# Dot-Matrix.net
KiCad netlist of a schematic drawn in EasyEDA
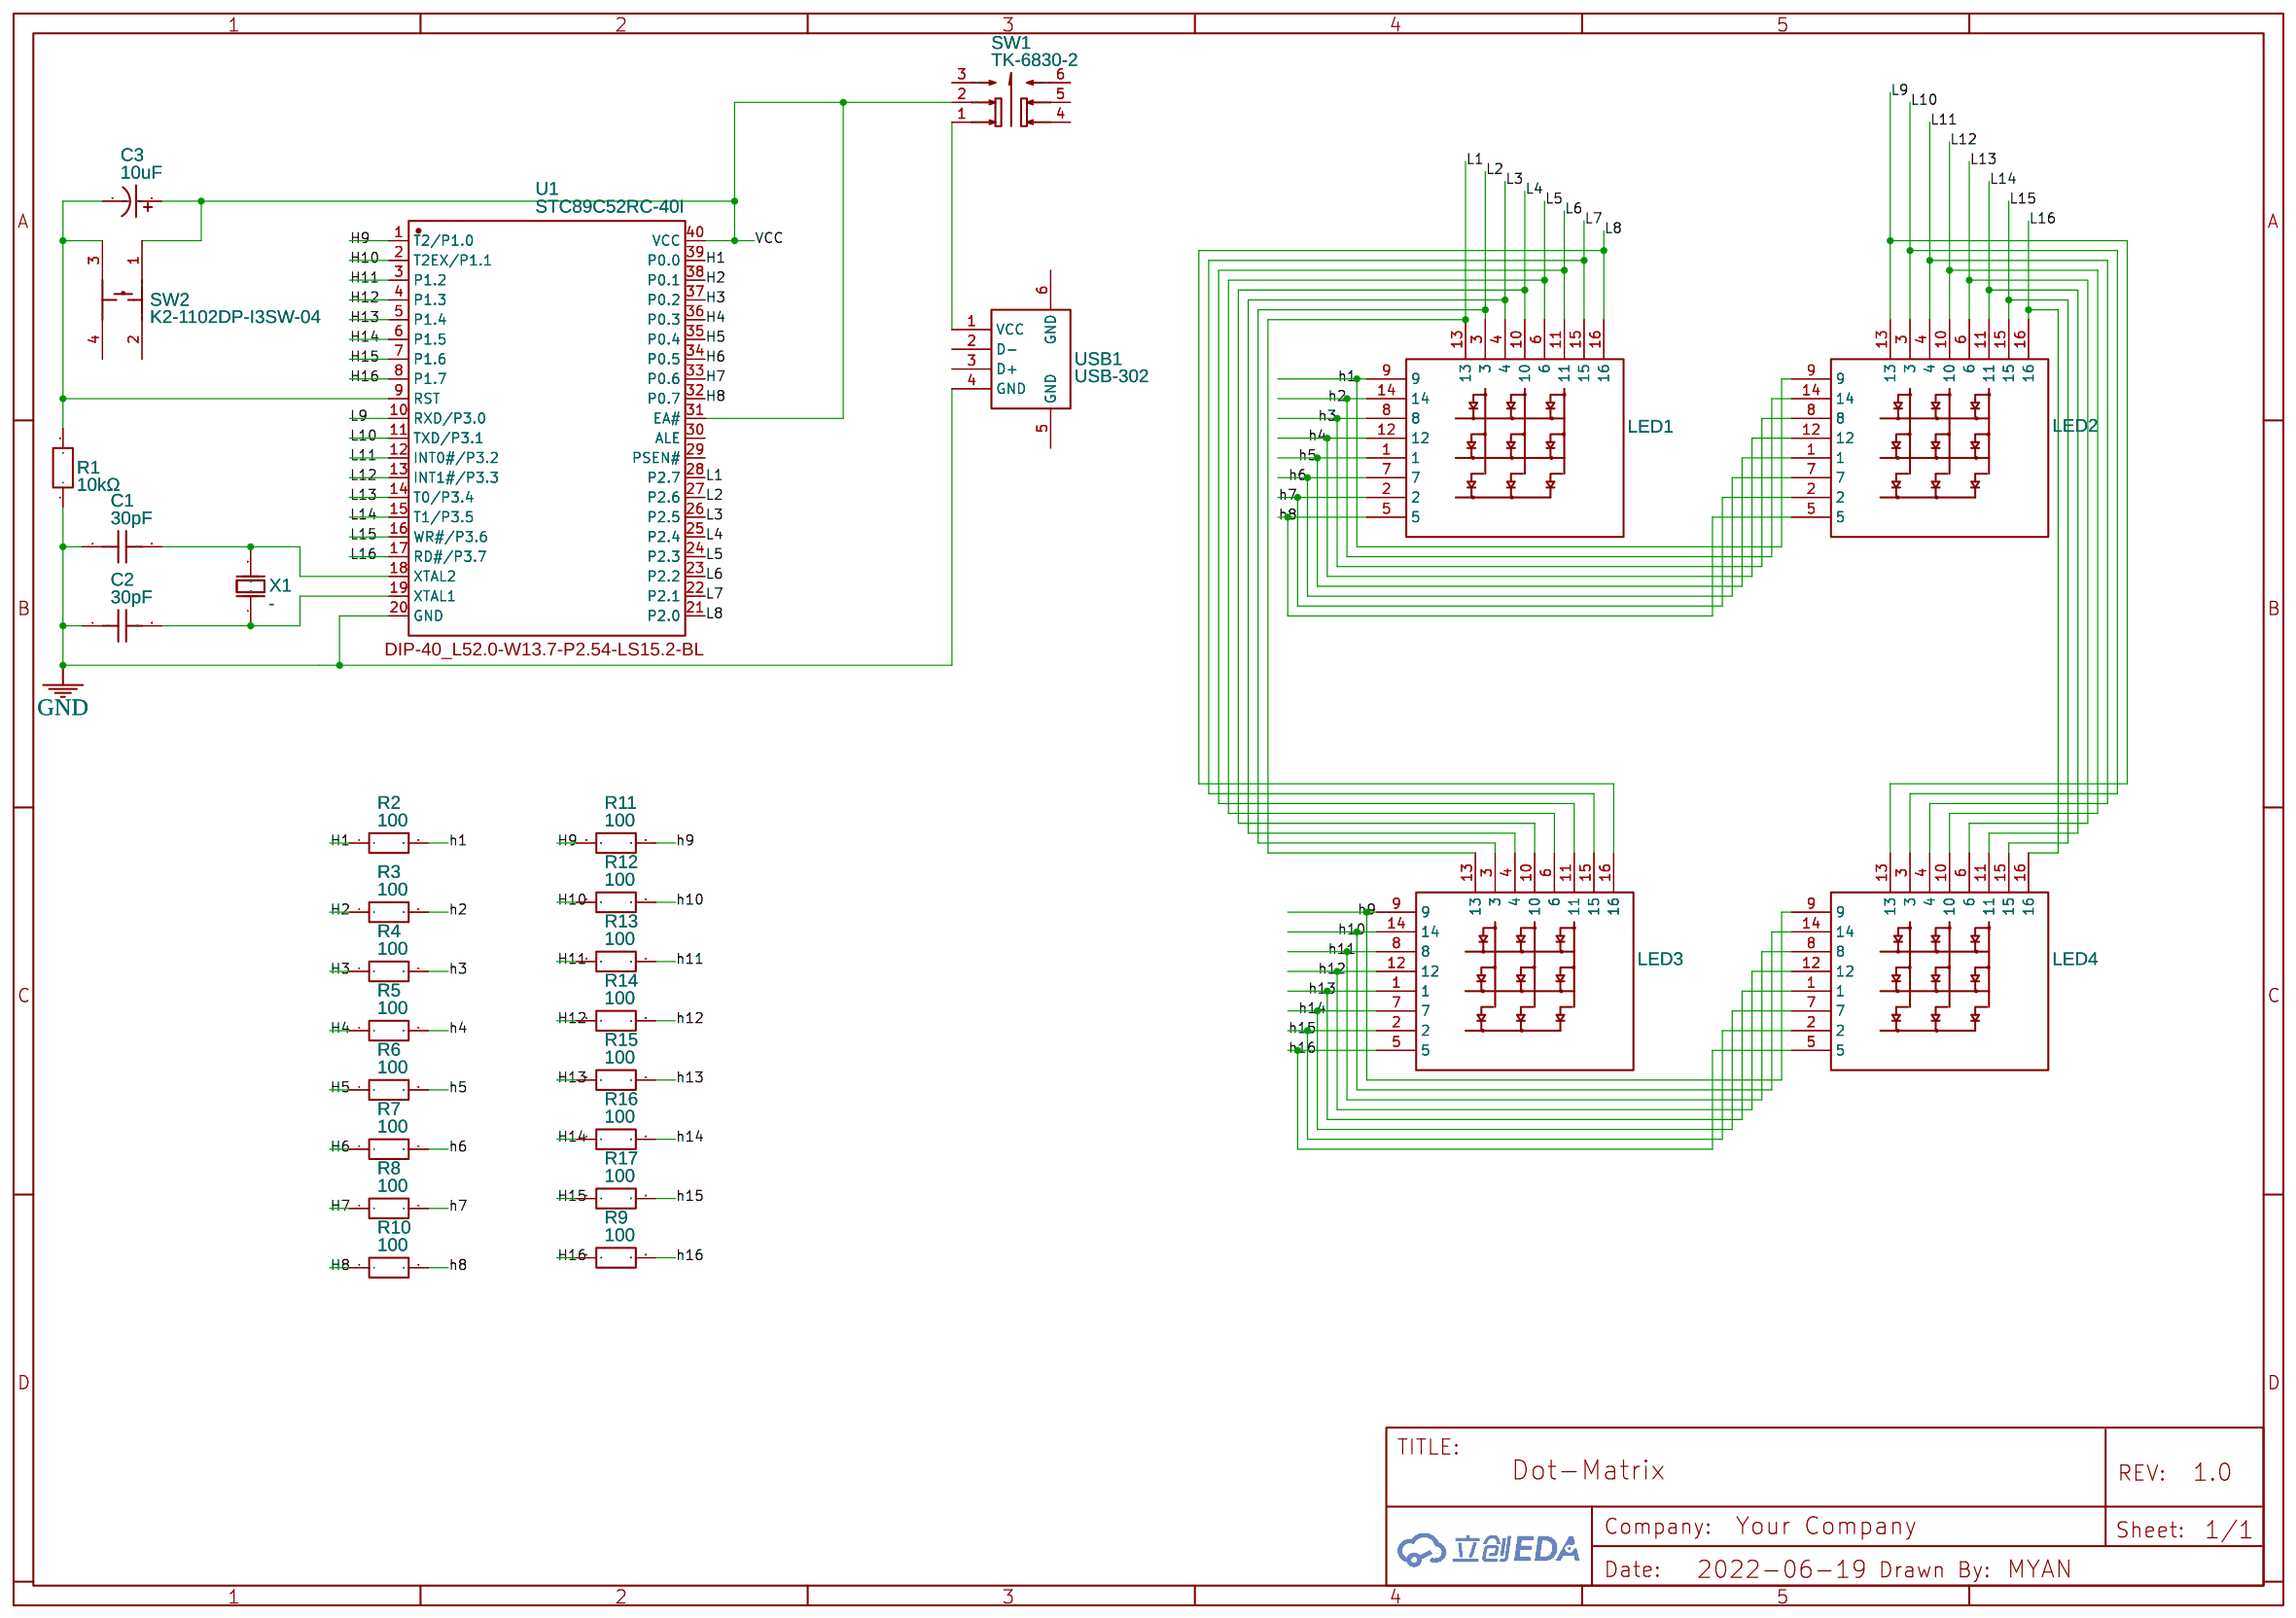
[diagram p0: schematic sheet]

(export (version "E")
  (design (tool "Eeschema 10.0.6"))
  (components
    (comp (ref "C1")
      (value "30pF")
      (fields
        (field (name "BOM_Manufacturer Part") "S07S1E330KN0B0S0N0")
        (field (name "BOM_Supplier Part") "C260735")
      )
      (libsource (lib "") (part "S07S1E330KN0B0S0N0"))
    )
    (comp (ref "C2")
      (value "30pF")
      (fields
        (field (name "BOM_Manufacturer Part") "S07S1E330KN0B0S0N0")
        (field (name "BOM_Supplier Part") "C260735")
      )
      (libsource (lib "") (part "S07S1E330KN0B0S0N0"))
    )
    (comp (ref "C3")
      (value "10uF")
      (fields (field (name "BOM_Manufacturer Part") "10uf/100V") (field (name "BOM_Supplier Part") "C2029"))
      (libsource (lib "") (part "10uf/100V"))
    )
    (comp (ref "LED1")
      (value "SLD0888DWC1BY_C2913073")
      (fields
        (field (name "BOM_Manufacturer Part") "SLD0888DWC1BY")
        (field (name "BOM_Supplier Part") "C2913073")
      )
      (libsource (lib "") (part "SLD0888DWC1BY_C2913073"))
    )
    (comp (ref "LED2")
      (value "SLD0888DWC1BY_C2913073")
      (fields
        (field (name "BOM_Manufacturer Part") "SLD0888DWC1BY")
        (field (name "BOM_Supplier Part") "C2913073")
      )
      (libsource (lib "") (part "SLD0888DWC1BY_C2913073"))
    )
    (comp (ref "LED3")
      (value "SLD0888DWC1BY_C2913073")
      (fields
        (field (name "BOM_Manufacturer Part") "SLD0888DWC1BY")
        (field (name "BOM_Supplier Part") "C2913073")
      )
      (libsource (lib "") (part "SLD0888DWC1BY_C2913073"))
    )
    (comp (ref "LED4")
      (value "SLD0888DWC1BY_C2913073")
      (fields
        (field (name "BOM_Manufacturer Part") "SLD0888DWC1BY")
        (field (name "BOM_Supplier Part") "C2913073")
      )
      (libsource (lib "") (part "SLD0888DWC1BY_C2913073"))
    )
    (comp (ref "R1")
      (value "10kΩ")
      (fields
        (field (name "BOM_Manufacturer Part") "MF3WS-10KΩ±1%T")
        (field (name "BOM_Supplier Part") "C714189")
      )
      (libsource (lib "") (part "MF3WS-10KΩ±1%T"))
    )
    (comp (ref "R2") (value "100") (libsource (lib "") (part "R_AXIAL-0.3_EU")))
    (comp (ref "R3") (value "100") (libsource (lib "") (part "R_AXIAL-0.3_EU")))
    (comp (ref "R4") (value "100") (libsource (lib "") (part "R_AXIAL-0.3_EU")))
    (comp (ref "R5") (value "100") (libsource (lib "") (part "R_AXIAL-0.3_EU")))
    (comp (ref "R6") (value "100") (libsource (lib "") (part "R_AXIAL-0.3_EU")))
    (comp (ref "R7") (value "100") (libsource (lib "") (part "R_AXIAL-0.3_EU")))
    (comp (ref "R8") (value "100") (libsource (lib "") (part "R_AXIAL-0.3_EU")))
    (comp (ref "R9") (value "100") (libsource (lib "") (part "R_AXIAL-0.3_EU")))
    (comp (ref "R10") (value "100") (libsource (lib "") (part "R_AXIAL-0.3_EU")))
    (comp (ref "R11") (value "100") (libsource (lib "") (part "R_AXIAL-0.3_EU")))
    (comp (ref "R12") (value "100") (libsource (lib "") (part "R_AXIAL-0.3_EU")))
    (comp (ref "R13") (value "100") (libsource (lib "") (part "R_AXIAL-0.3_EU")))
    (comp (ref "R14") (value "100") (libsource (lib "") (part "R_AXIAL-0.3_EU")))
    (comp (ref "R15") (value "100") (libsource (lib "") (part "R_AXIAL-0.3_EU")))
    (comp (ref "R16") (value "100") (libsource (lib "") (part "R_AXIAL-0.3_EU")))
    (comp (ref "R17") (value "100") (libsource (lib "") (part "R_AXIAL-0.3_EU")))
    (comp (ref "SW1")
      (value "TK-6830-2")
      (fields (field (name "BOM_Supplier Part") "C528789"))
      (libsource (lib "") (part "TK-6830-2"))
    )
    (comp (ref "SW2")
      (value "K2-1102DP-I3SW-04")
      (fields (field (name "BOM_Supplier Part") "C2685962"))
      (libsource (lib "") (part "K2-1102DP-I3SW-04"))
    )
    (comp (ref "U1")
      (value "STC89C52RC-40I")
      (fields (field (name "BOM_Supplier Part") "C14022"))
      (libsource (lib "") (part "STC89C52RC-40I"))
    )
    (comp (ref "USB1")
      (value "USB-302")
      (fields (field (name "BOM_Supplier Part") "C112456"))
      (libsource (lib "") (part "USB-302"))
    )
    (comp (ref "X1")
      (value "-")
      (fields
        (field (name "BOM_Manufacturer Part") "ESA11.0592F20M25F")
        (field (name "BOM_Supplier Part") "C353687")
      )
      (libsource (lib "") (part "ESA11.0592F20M25F"))
    )
  )
  (nets
    (net (code "1") (name "/H1") (class "Default")
      (node (ref "R2") (pin "1") (pinfunction "1_1") (pintype "unspecified"))
      (node (ref "U1") (pin "39") (pinfunction "P0.0_39") (pintype "unspecified"))
    )
    (net (code "2") (name "/H2") (class "Default")
      (node (ref "R3") (pin "1") (pinfunction "1_1") (pintype "unspecified"))
      (node (ref "U1") (pin "38") (pinfunction "P0.1_38") (pintype "unspecified"))
    )
    (net (code "3") (name "/H3") (class "Default")
      (node (ref "R4") (pin "1") (pinfunction "1_1") (pintype "unspecified"))
      (node (ref "U1") (pin "37") (pinfunction "P0.2_37") (pintype "unspecified"))
    )
    (net (code "4") (name "/H4") (class "Default")
      (node (ref "R5") (pin "1") (pinfunction "1_1") (pintype "unspecified"))
      (node (ref "U1") (pin "36") (pinfunction "P0.3_36") (pintype "unspecified"))
    )
    (net (code "5") (name "/H5") (class "Default")
      (node (ref "R6") (pin "1") (pinfunction "1_1") (pintype "unspecified"))
      (node (ref "U1") (pin "35") (pinfunction "P0.4_35") (pintype "unspecified"))
    )
    (net (code "6") (name "/H6") (class "Default")
      (node (ref "R7") (pin "1") (pinfunction "1_1") (pintype "unspecified"))
      (node (ref "U1") (pin "34") (pinfunction "P0.5_34") (pintype "unspecified"))
    )
    (net (code "7") (name "/H7") (class "Default")
      (node (ref "R8") (pin "1") (pinfunction "1_1") (pintype "unspecified"))
      (node (ref "U1") (pin "33") (pinfunction "P0.6_33") (pintype "unspecified"))
    )
    (net (code "8") (name "/H8") (class "Default")
      (node (ref "R10") (pin "1") (pinfunction "1_1") (pintype "unspecified"))
      (node (ref "U1") (pin "32") (pinfunction "P0.7_32") (pintype "unspecified"))
    )
    (net (code "9") (name "/H9") (class "Default")
      (node (ref "R11") (pin "1") (pinfunction "1_1") (pintype "unspecified"))
      (node (ref "U1") (pin "1") (pinfunction "T2/P1.0_1") (pintype "unspecified"))
    )
    (net (code "10") (name "/H10") (class "Default")
      (node (ref "R12") (pin "1") (pinfunction "1_1") (pintype "unspecified"))
      (node (ref "U1") (pin "2") (pinfunction "T2EX/P1.1_2") (pintype "unspecified"))
    )
    (net (code "11") (name "/H11") (class "Default")
      (node (ref "R13") (pin "1") (pinfunction "1_1") (pintype "unspecified"))
      (node (ref "U1") (pin "3") (pinfunction "P1.2_3") (pintype "unspecified"))
    )
    (net (code "12") (name "/H12") (class "Default")
      (node (ref "R14") (pin "1") (pinfunction "1_1") (pintype "unspecified"))
      (node (ref "U1") (pin "4") (pinfunction "P1.3_4") (pintype "unspecified"))
    )
    (net (code "13") (name "/H13") (class "Default")
      (node (ref "R15") (pin "1") (pinfunction "1_1") (pintype "unspecified"))
      (node (ref "U1") (pin "5") (pinfunction "P1.4_5") (pintype "unspecified"))
    )
    (net (code "14") (name "/H14") (class "Default")
      (node (ref "R16") (pin "1") (pinfunction "1_1") (pintype "unspecified"))
      (node (ref "U1") (pin "6") (pinfunction "P1.5_6") (pintype "unspecified"))
    )
    (net (code "15") (name "/H15") (class "Default")
      (node (ref "R17") (pin "1") (pinfunction "1_1") (pintype "unspecified"))
      (node (ref "U1") (pin "7") (pinfunction "P1.6_7") (pintype "unspecified"))
    )
    (net (code "16") (name "/H16") (class "Default")
      (node (ref "R9") (pin "1") (pinfunction "1_1") (pintype "unspecified"))
      (node (ref "U1") (pin "8") (pinfunction "P1.7_8") (pintype "unspecified"))
    )
    (net (code "17") (name "/L1") (class "Default")
      (node (ref "LED1") (pin "13") (pinfunction "13_13") (pintype "unspecified"))
      (node (ref "LED3") (pin "13") (pinfunction "13_13") (pintype "unspecified"))
      (node (ref "U1") (pin "28") (pinfunction "P2.7_28") (pintype "unspecified"))
    )
    (net (code "18") (name "/L2") (class "Default")
      (node (ref "LED1") (pin "3") (pinfunction "3_3") (pintype "unspecified"))
      (node (ref "LED3") (pin "3") (pinfunction "3_3") (pintype "unspecified"))
      (node (ref "U1") (pin "27") (pinfunction "P2.6_27") (pintype "unspecified"))
    )
    (net (code "19") (name "/L3") (class "Default")
      (node (ref "LED1") (pin "4") (pinfunction "4_4") (pintype "unspecified"))
      (node (ref "LED3") (pin "4") (pinfunction "4_4") (pintype "unspecified"))
      (node (ref "U1") (pin "26") (pinfunction "P2.5_26") (pintype "unspecified"))
    )
    (net (code "20") (name "/L4") (class "Default")
      (node (ref "LED1") (pin "10") (pinfunction "10_10") (pintype "unspecified"))
      (node (ref "LED3") (pin "10") (pinfunction "10_10") (pintype "unspecified"))
      (node (ref "U1") (pin "25") (pinfunction "P2.4_25") (pintype "unspecified"))
    )
    (net (code "21") (name "/L5") (class "Default")
      (node (ref "LED1") (pin "6") (pinfunction "6_6") (pintype "unspecified"))
      (node (ref "LED3") (pin "6") (pinfunction "6_6") (pintype "unspecified"))
      (node (ref "U1") (pin "24") (pinfunction "P2.3_24") (pintype "unspecified"))
    )
    (net (code "22") (name "/L6") (class "Default")
      (node (ref "LED1") (pin "11") (pinfunction "11_11") (pintype "unspecified"))
      (node (ref "LED3") (pin "11") (pinfunction "11_11") (pintype "unspecified"))
      (node (ref "U1") (pin "23") (pinfunction "P2.2_23") (pintype "unspecified"))
    )
    (net (code "23") (name "/L7") (class "Default")
      (node (ref "LED1") (pin "15") (pinfunction "15_15") (pintype "unspecified"))
      (node (ref "LED3") (pin "15") (pinfunction "15_15") (pintype "unspecified"))
      (node (ref "U1") (pin "22") (pinfunction "P2.1_22") (pintype "unspecified"))
    )
    (net (code "24") (name "/L8") (class "Default")
      (node (ref "LED1") (pin "16") (pinfunction "16_16") (pintype "unspecified"))
      (node (ref "LED3") (pin "16") (pinfunction "16_16") (pintype "unspecified"))
      (node (ref "U1") (pin "21") (pinfunction "P2.0_21") (pintype "unspecified"))
    )
    (net (code "25") (name "/L9") (class "Default")
      (node (ref "LED2") (pin "13") (pinfunction "13_13") (pintype "unspecified"))
      (node (ref "LED4") (pin "13") (pinfunction "13_13") (pintype "unspecified"))
      (node (ref "U1") (pin "10") (pinfunction "RXD/P3.0_10") (pintype "unspecified"))
    )
    (net (code "26") (name "/L10") (class "Default")
      (node (ref "LED2") (pin "3") (pinfunction "3_3") (pintype "unspecified"))
      (node (ref "LED4") (pin "3") (pinfunction "3_3") (pintype "unspecified"))
      (node (ref "U1") (pin "11") (pinfunction "TXD/P3.1_11") (pintype "unspecified"))
    )
    (net (code "27") (name "/L11") (class "Default")
      (node (ref "LED2") (pin "4") (pinfunction "4_4") (pintype "unspecified"))
      (node (ref "LED4") (pin "4") (pinfunction "4_4") (pintype "unspecified"))
      (node (ref "U1") (pin "12") (pinfunction "INT0#/P3.2_12") (pintype "unspecified"))
    )
    (net (code "28") (name "/L12") (class "Default")
      (node (ref "LED2") (pin "10") (pinfunction "10_10") (pintype "unspecified"))
      (node (ref "LED4") (pin "10") (pinfunction "10_10") (pintype "unspecified"))
      (node (ref "U1") (pin "13") (pinfunction "INT1#/P3.3_13") (pintype "unspecified"))
    )
    (net (code "29") (name "/L13") (class "Default")
      (node (ref "LED2") (pin "6") (pinfunction "6_6") (pintype "unspecified"))
      (node (ref "LED4") (pin "6") (pinfunction "6_6") (pintype "unspecified"))
      (node (ref "U1") (pin "14") (pinfunction "T0/P3.4_14") (pintype "unspecified"))
    )
    (net (code "30") (name "/L14") (class "Default")
      (node (ref "LED2") (pin "11") (pinfunction "11_11") (pintype "unspecified"))
      (node (ref "LED4") (pin "11") (pinfunction "11_11") (pintype "unspecified"))
      (node (ref "U1") (pin "15") (pinfunction "T1/P3.5_15") (pintype "unspecified"))
    )
    (net (code "31") (name "/L15") (class "Default")
      (node (ref "LED2") (pin "15") (pinfunction "15_15") (pintype "unspecified"))
      (node (ref "LED4") (pin "15") (pinfunction "15_15") (pintype "unspecified"))
      (node (ref "U1") (pin "16") (pinfunction "WR#/P3.6_16") (pintype "unspecified"))
    )
    (net (code "32") (name "/L16") (class "Default")
      (node (ref "LED2") (pin "16") (pinfunction "16_16") (pintype "unspecified"))
      (node (ref "LED4") (pin "16") (pinfunction "16_16") (pintype "unspecified"))
      (node (ref "U1") (pin "17") (pinfunction "RD#/P3.7_17") (pintype "unspecified"))
    )
    (net (code "33") (name "/VCC") (class "Default")
      (node (ref "C3") (pin "1") (pinfunction "1_1") (pintype "input"))
      (node (ref "SW1") (pin "2") (pinfunction "2_2") (pintype "unspecified"))
      (node (ref "SW2") (pin "1") (pinfunction "1_1") (pintype "unspecified"))
      (node (ref "U1") (pin "31") (pinfunction "EA#_31") (pintype "unspecified"))
      (node (ref "U1") (pin "40") (pinfunction "VCC_40") (pintype "unspecified"))
    )
    (net (code "34") (name "/h1") (class "Default")
      (node (ref "LED1") (pin "9") (pinfunction "9_9") (pintype "unspecified"))
      (node (ref "LED2") (pin "9") (pinfunction "9_9") (pintype "unspecified"))
      (node (ref "R2") (pin "2") (pinfunction "2_2") (pintype "unspecified"))
    )
    (net (code "35") (name "/h2") (class "Default")
      (node (ref "LED1") (pin "14") (pinfunction "14_14") (pintype "unspecified"))
      (node (ref "LED2") (pin "14") (pinfunction "14_14") (pintype "unspecified"))
      (node (ref "R3") (pin "2") (pinfunction "2_2") (pintype "unspecified"))
    )
    (net (code "36") (name "/h3") (class "Default")
      (node (ref "LED1") (pin "8") (pinfunction "8_8") (pintype "unspecified"))
      (node (ref "LED2") (pin "8") (pinfunction "8_8") (pintype "unspecified"))
      (node (ref "R4") (pin "2") (pinfunction "2_2") (pintype "unspecified"))
    )
    (net (code "37") (name "/h4") (class "Default")
      (node (ref "LED1") (pin "12") (pinfunction "12_12") (pintype "unspecified"))
      (node (ref "LED2") (pin "12") (pinfunction "12_12") (pintype "unspecified"))
      (node (ref "R5") (pin "2") (pinfunction "2_2") (pintype "unspecified"))
    )
    (net (code "38") (name "/h5") (class "Default")
      (node (ref "LED1") (pin "1") (pinfunction "1_1") (pintype "unspecified"))
      (node (ref "LED2") (pin "1") (pinfunction "1_1") (pintype "unspecified"))
      (node (ref "R6") (pin "2") (pinfunction "2_2") (pintype "unspecified"))
    )
    (net (code "39") (name "/h6") (class "Default")
      (node (ref "LED1") (pin "7") (pinfunction "7_7") (pintype "unspecified"))
      (node (ref "LED2") (pin "7") (pinfunction "7_7") (pintype "unspecified"))
      (node (ref "R7") (pin "2") (pinfunction "2_2") (pintype "unspecified"))
    )
    (net (code "40") (name "/h7") (class "Default")
      (node (ref "LED1") (pin "2") (pinfunction "2_2") (pintype "unspecified"))
      (node (ref "LED2") (pin "2") (pinfunction "2_2") (pintype "unspecified"))
      (node (ref "R8") (pin "2") (pinfunction "2_2") (pintype "unspecified"))
    )
    (net (code "41") (name "/h8") (class "Default")
      (node (ref "LED1") (pin "5") (pinfunction "5_5") (pintype "unspecified"))
      (node (ref "LED2") (pin "5") (pinfunction "5_5") (pintype "unspecified"))
      (node (ref "R10") (pin "2") (pinfunction "2_2") (pintype "unspecified"))
    )
    (net (code "42") (name "/h9") (class "Default")
      (node (ref "LED3") (pin "9") (pinfunction "9_9") (pintype "unspecified"))
      (node (ref "LED4") (pin "9") (pinfunction "9_9") (pintype "unspecified"))
      (node (ref "R11") (pin "2") (pinfunction "2_2") (pintype "unspecified"))
    )
    (net (code "43") (name "/h10") (class "Default")
      (node (ref "LED3") (pin "14") (pinfunction "14_14") (pintype "unspecified"))
      (node (ref "LED4") (pin "14") (pinfunction "14_14") (pintype "unspecified"))
      (node (ref "R12") (pin "2") (pinfunction "2_2") (pintype "unspecified"))
    )
    (net (code "44") (name "/h11") (class "Default")
      (node (ref "LED3") (pin "8") (pinfunction "8_8") (pintype "unspecified"))
      (node (ref "LED4") (pin "8") (pinfunction "8_8") (pintype "unspecified"))
      (node (ref "R13") (pin "2") (pinfunction "2_2") (pintype "unspecified"))
    )
    (net (code "45") (name "/h12") (class "Default")
      (node (ref "LED3") (pin "12") (pinfunction "12_12") (pintype "unspecified"))
      (node (ref "LED4") (pin "12") (pinfunction "12_12") (pintype "unspecified"))
      (node (ref "R14") (pin "2") (pinfunction "2_2") (pintype "unspecified"))
    )
    (net (code "46") (name "/h13") (class "Default")
      (node (ref "LED3") (pin "1") (pinfunction "1_1") (pintype "unspecified"))
      (node (ref "LED4") (pin "1") (pinfunction "1_1") (pintype "unspecified"))
      (node (ref "R15") (pin "2") (pinfunction "2_2") (pintype "unspecified"))
    )
    (net (code "47") (name "/h14") (class "Default")
      (node (ref "LED3") (pin "7") (pinfunction "7_7") (pintype "unspecified"))
      (node (ref "LED4") (pin "7") (pinfunction "7_7") (pintype "unspecified"))
      (node (ref "R16") (pin "2") (pinfunction "2_2") (pintype "unspecified"))
    )
    (net (code "48") (name "/h15") (class "Default")
      (node (ref "LED3") (pin "2") (pinfunction "2_2") (pintype "unspecified"))
      (node (ref "LED4") (pin "2") (pinfunction "2_2") (pintype "unspecified"))
      (node (ref "R17") (pin "2") (pinfunction "2_2") (pintype "unspecified"))
    )
    (net (code "49") (name "/h16") (class "Default")
      (node (ref "LED3") (pin "5") (pinfunction "5_5") (pintype "unspecified"))
      (node (ref "LED4") (pin "5") (pinfunction "5_5") (pintype "unspecified"))
      (node (ref "R9") (pin "2") (pinfunction "2_2") (pintype "unspecified"))
    )
    (net (code "50") (name "GND") (class "Default")
      (node (ref "C1") (pin "1") (pinfunction "1_1") (pintype "unspecified"))
      (node (ref "C2") (pin "1") (pinfunction "1_1") (pintype "unspecified"))
      (node (ref "R1") (pin "1") (pinfunction "1_1") (pintype "unspecified"))
      (node (ref "U1") (pin "20") (pinfunction "GND_20") (pintype "unspecified"))
      (node (ref "USB1") (pin "4") (pinfunction "GND_4") (pintype "unspecified"))
    )
    (net (code "51") (name "Net-(U1-RST)") (class "Default")
      (node (ref "C3") (pin "2") (pinfunction "2_2") (pintype "input"))
      (node (ref "R1") (pin "2") (pinfunction "2_2") (pintype "unspecified"))
      (node (ref "SW2") (pin "3") (pinfunction "3_3") (pintype "unspecified"))
      (node (ref "U1") (pin "9") (pinfunction "RST_9") (pintype "unspecified"))
    )
    (net (code "52") (name "Net-(U1-XTAL1)") (class "Default")
      (node (ref "C2") (pin "2") (pinfunction "2_2") (pintype "unspecified"))
      (node (ref "U1") (pin "19") (pinfunction "XTAL1_19") (pintype "unspecified"))
      (node (ref "X1") (pin "1") (pinfunction "OSC1_1") (pintype "input"))
    )
    (net (code "53") (name "Net-(U1-XTAL2)") (class "Default")
      (node (ref "C1") (pin "2") (pinfunction "2_2") (pintype "unspecified"))
      (node (ref "U1") (pin "18") (pinfunction "XTAL2_18") (pintype "unspecified"))
      (node (ref "X1") (pin "2") (pinfunction "OSC2_2") (pintype "input"))
    )
    (net (code "54") (name "Net-(USB1-VCC)") (class "Default")
      (node (ref "SW1") (pin "1") (pinfunction "1_1") (pintype "unspecified"))
      (node (ref "USB1") (pin "1") (pinfunction "VCC_1") (pintype "unspecified"))
    )
    (net (code "55") (name "unconnected-(SW1-Pad3)") (class "Default")
      (node (ref "SW1") (pin "3") (pinfunction "3_3") (pintype "unspecified"))
    )
    (net (code "56") (name "unconnected-(SW1-Pad4)") (class "Default")
      (node (ref "SW1") (pin "4") (pinfunction "4_4") (pintype "unspecified"))
    )
    (net (code "57") (name "unconnected-(SW1-Pad5)") (class "Default")
      (node (ref "SW1") (pin "5") (pinfunction "5_5") (pintype "unspecified"))
    )
    (net (code "58") (name "unconnected-(SW1-Pad6)") (class "Default")
      (node (ref "SW1") (pin "6") (pinfunction "6_6") (pintype "unspecified"))
    )
    (net (code "59") (name "unconnected-(SW2-Pad2)") (class "Default")
      (node (ref "SW2") (pin "2") (pinfunction "2_2") (pintype "unspecified"))
    )
    (net (code "60") (name "unconnected-(SW2-Pad4)") (class "Default")
      (node (ref "SW2") (pin "4") (pinfunction "4_4") (pintype "unspecified"))
    )
    (net (code "61") (name "unconnected-(U1-ALE-Pad30)") (class "Default")
      (node (ref "U1") (pin "30") (pinfunction "ALE_30") (pintype "unspecified"))
    )
    (net (code "62") (name "unconnected-(U1-PSEN#-Pad29)") (class "Default")
      (node (ref "U1") (pin "29") (pinfunction "PSEN#_29") (pintype "unspecified"))
    )
    (net (code "63") (name "unconnected-(USB1-D+-Pad3)") (class "Default")
      (node (ref "USB1") (pin "3") (pinfunction "D+_3") (pintype "unspecified"))
    )
    (net (code "64") (name "unconnected-(USB1-D--Pad2)") (class "Default")
      (node (ref "USB1") (pin "2") (pinfunction "D-_2") (pintype "unspecified"))
    )
    (net (code "65") (name "unconnected-(USB1-GND-Pad5)") (class "Default")
      (node (ref "USB1") (pin "5") (pinfunction "GND_5") (pintype "unspecified"))
    )
    (net (code "66") (name "unconnected-(USB1-GND-Pad6)") (class "Default")
      (node (ref "USB1") (pin "6") (pinfunction "GND_6") (pintype "unspecified"))
    )
  )
)
